# thar_board_general_mk1.net
KiCad netlist of a schematic drawn in EAGLE
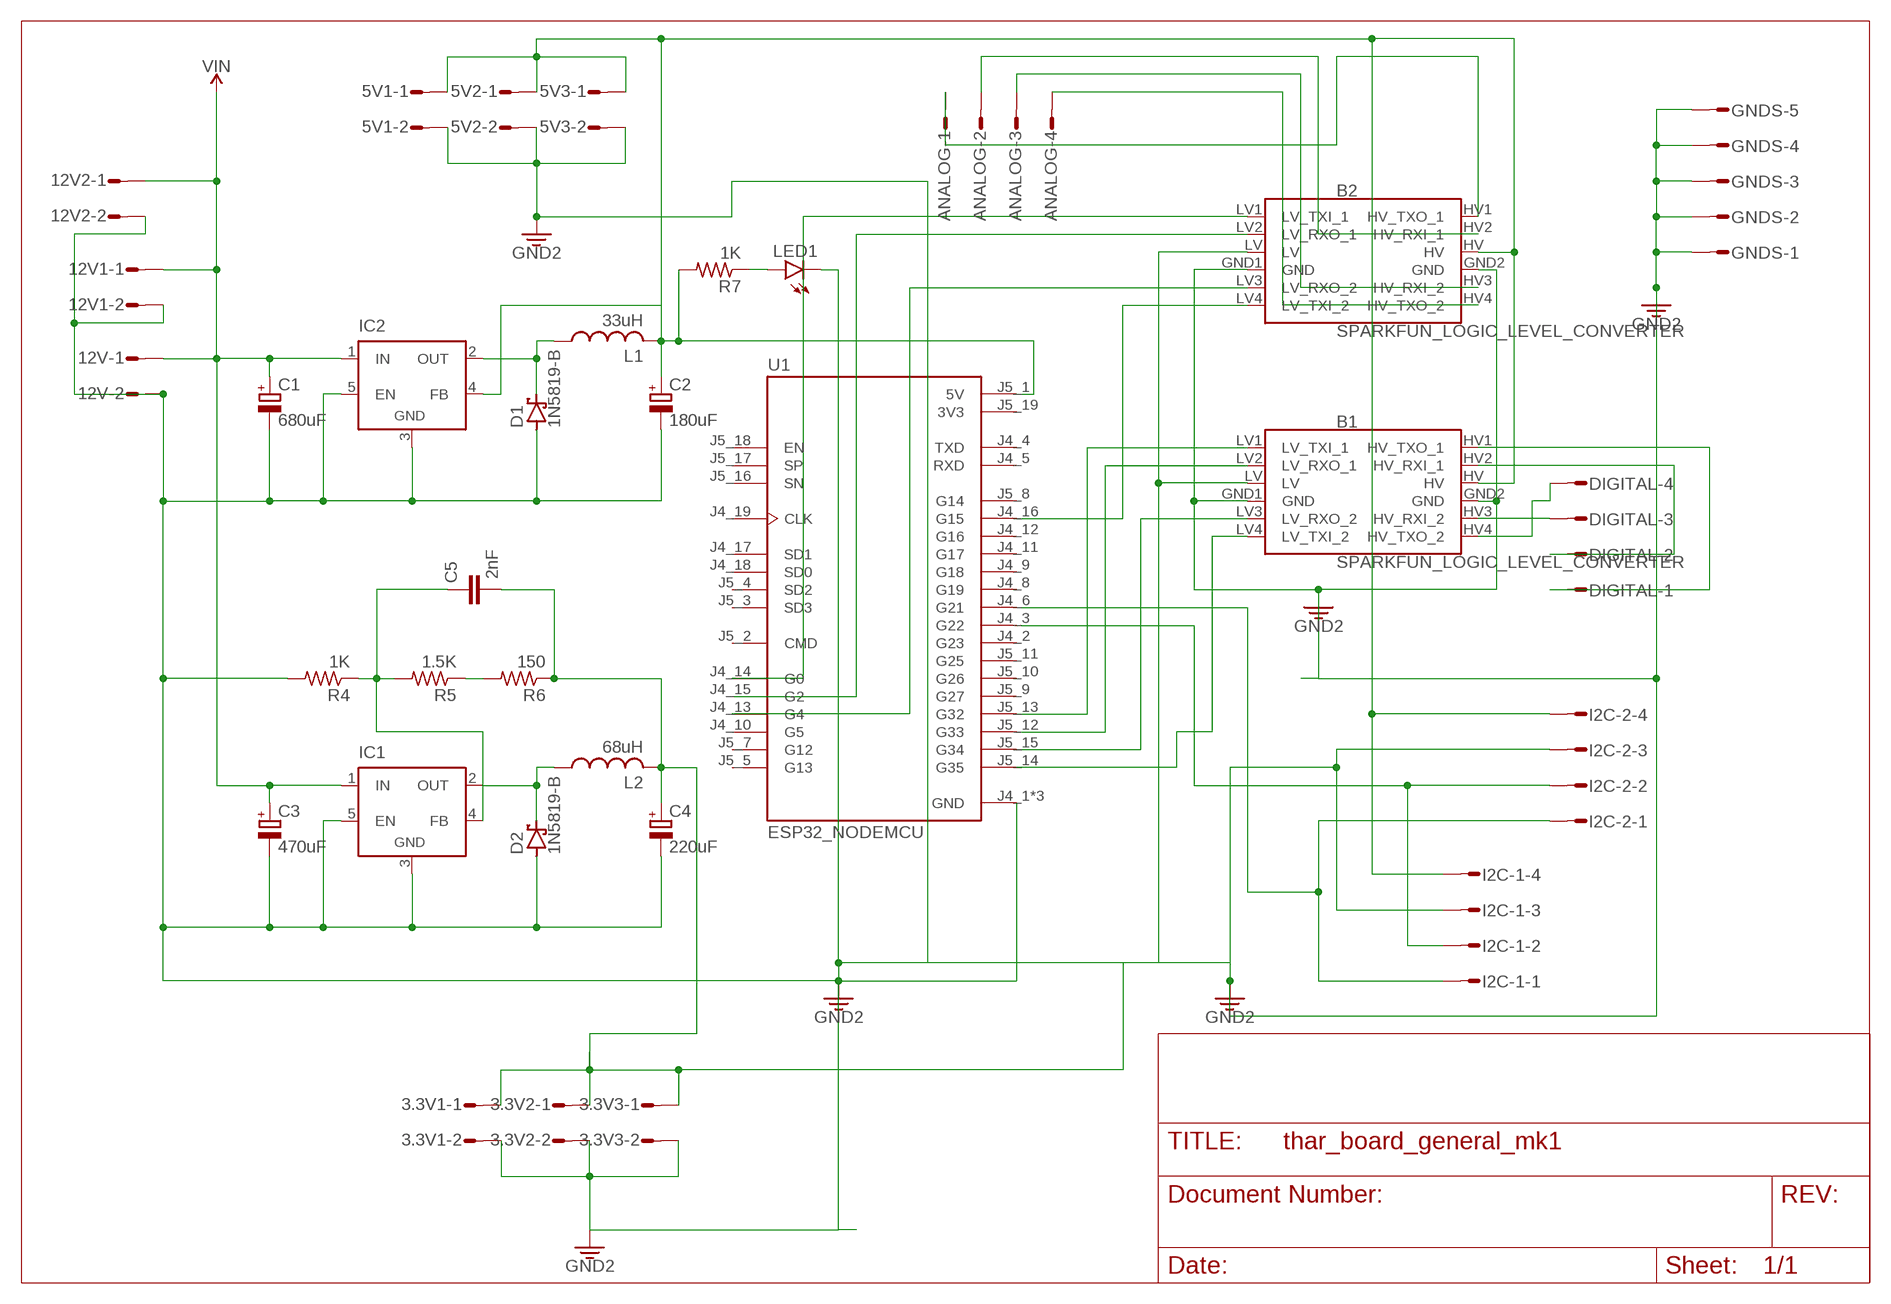
[diagram p0: schematic, sheet 1]

(export (version "E")
  (design (tool "Eeschema 10.0.6"))
  (components
    (comp (ref "3.3V1")
      (value "L02P")
      (footprint "eagle-import:L02P")
      (libsource (lib "eagle-import") (part "L02P"))
    )
    (comp (ref "3.3V2")
      (value "L02P")
      (footprint "eagle-import:L02P")
      (libsource (lib "eagle-import") (part "L02P"))
    )
    (comp (ref "3.3V3")
      (value "L02P")
      (footprint "eagle-import:L02P")
      (libsource (lib "eagle-import") (part "L02P"))
    )
    (comp (ref "5V1")
      (value "L02P")
      (footprint "eagle-import:L02P")
      (libsource (lib "eagle-import") (part "L02P"))
    )
    (comp (ref "5V2")
      (value "L02P")
      (footprint "eagle-import:L02P")
      (libsource (lib "eagle-import") (part "L02P"))
    )
    (comp (ref "5V3")
      (value "L02P")
      (footprint "eagle-import:L02P")
      (libsource (lib "eagle-import") (part "L02P"))
    )
    (comp (ref "12V")
      (value "L02P")
      (footprint "eagle-import:L02P")
      (libsource (lib "eagle-import") (part "L02P"))
    )
    (comp (ref "12V1")
      (value "L02P")
      (footprint "eagle-import:L02P")
      (libsource (lib "eagle-import") (part "L02P"))
    )
    (comp (ref "12V2")
      (value "L02P")
      (footprint "eagle-import:L02P")
      (libsource (lib "eagle-import") (part "L02P"))
    )
    (comp (ref "ANALOG")
      (value "L04P")
      (footprint "eagle-import:L04P")
      (libsource (lib "eagle-import") (part "L04P"))
    )
    (comp (ref "B1")
      (value "SPARKFUN_LOGIC_LEVEL_CONVERTER")
      (footprint "eagle-import:SPARKFUN_LOGIC_LEVEL_CONVERTER")
      (libsource (lib "eagle-import") (part "SPARKFUN_LOGIC_LEVEL_CONVERTER"))
    )
    (comp (ref "B2")
      (value "SPARKFUN_LOGIC_LEVEL_CONVERTER")
      (footprint "eagle-import:SPARKFUN_LOGIC_LEVEL_CONVERTER")
      (libsource (lib "eagle-import") (part "SPARKFUN_LOGIC_LEVEL_CONVERTER"))
    )
    (comp (ref "C1")
      (value "680uF")
      (footprint "eagle-import:E2,5-7")
      (libsource (lib "eagle-import") (part "CPOL-EUE2.5-7"))
    )
    (comp (ref "C2")
      (value "180uF")
      (footprint "eagle-import:E2,5-7")
      (libsource (lib "eagle-import") (part "CPOL-EUE2.5-7"))
    )
    (comp (ref "C3")
      (value "470uF")
      (footprint "eagle-import:E2,5-7")
      (libsource (lib "eagle-import") (part "CPOL-EUE2.5-7"))
    )
    (comp (ref "C4")
      (value "220uF")
      (footprint "eagle-import:E2,5-7")
      (libsource (lib "eagle-import") (part "CPOL-EUE2.5-7"))
    )
    (comp (ref "C5")
      (value "2nF")
      (footprint "eagle-import:C025-025X050")
      (libsource (lib "eagle-import") (part "C-EU025-025X050"))
    )
    (comp (ref "D1")
      (value "1N5819-B")
      (footprint "eagle-import:DO41-7.6")
      (libsource (lib "eagle-import") (part "1N5819-B"))
    )
    (comp (ref "D2")
      (value "1N5819-B")
      (footprint "eagle-import:DO41-7.6")
      (libsource (lib "eagle-import") (part "1N5819-B"))
    )
    (comp (ref "DIGITAL")
      (value "L04P")
      (footprint "eagle-import:L04P")
      (libsource (lib "eagle-import") (part "L04P"))
    )
    (comp (ref "GNDS")
      (value "L05P")
      (footprint "eagle-import:L05P")
      (libsource (lib "eagle-import") (part "L05P"))
    )
    (comp (ref "I2C-1")
      (value "L04P")
      (footprint "eagle-import:L04P")
      (libsource (lib "eagle-import") (part "L04P"))
    )
    (comp (ref "I2C-2")
      (value "L04P")
      (footprint "eagle-import:L04P")
      (libsource (lib "eagle-import") (part "L04P"))
    )
    (comp (ref "IC1")
      (value "LM2596TH")
      (footprint "eagle-import:TO220-52")
      (libsource (lib "eagle-import") (part "LM2596TH"))
    )
    (comp (ref "IC2")
      (value "LM2596TH")
      (footprint "eagle-import:TO220-52")
      (libsource (lib "eagle-import") (part "LM2596TH"))
    )
    (comp (ref "L1")
      (value "33uH")
      (footprint "eagle-import:TFI0410")
      (libsource (lib "eagle-import") (part "L-USTFI0410"))
    )
    (comp (ref "L2")
      (value "68uH")
      (footprint "eagle-import:TFI0410")
      (libsource (lib "eagle-import") (part "L-USTFI0410"))
    )
    (comp (ref "LED1")
      (value "LED3MM")
      (footprint "eagle-import:LED3MM")
      (libsource (lib "eagle-import") (part "LED3MM"))
    )
    (comp (ref "R4")
      (value "1K")
      (footprint "eagle-import:0207_10")
      (libsource (lib "eagle-import") (part "R-US_0207/10"))
    )
    (comp (ref "R5")
      (value "1.5K")
      (footprint "eagle-import:0207_10")
      (libsource (lib "eagle-import") (part "R-US_0207/10"))
    )
    (comp (ref "R6")
      (value "150")
      (footprint "eagle-import:0207_10")
      (libsource (lib "eagle-import") (part "R-US_0207/10"))
    )
    (comp (ref "R7")
      (value "1K")
      (footprint "eagle-import:0207_10")
      (libsource (lib "eagle-import") (part "R-US_0207/10"))
    )
    (comp (ref "U1")
      (value "ESP32_NODEMCU")
      (footprint "eagle-import:MODULE_ESP32_NODEMCU")
      (fields (field (name "MF") "Espressif Systems") (field (name "MP") "ESP32 NodeMCU"))
      (libsource (lib "eagle-import") (part "ESP32_NODEMCU"))
    )
  )
  (nets
    (net (code "1") (name "/3V3") (class "Default")
      (node (ref "U1") (pin "J5_19") (pinfunction "3V3_J5_19") (pintype "power_in"))
    )
    (net (code "2") (name "GND2") (class "Default")
      (node (ref "12V") (pin "2") (pinfunction "S_2") (pintype "passive"))
      (node (ref "12V1") (pin "2") (pinfunction "S_2") (pintype "passive"))
      (node (ref "12V2") (pin "2") (pinfunction "S_2") (pintype "passive"))
      (node (ref "3.3V1") (pin "2") (pinfunction "S_2") (pintype "passive"))
      (node (ref "3.3V2") (pin "2") (pinfunction "S_2") (pintype "passive"))
      (node (ref "3.3V3") (pin "2") (pinfunction "S_2") (pintype "passive"))
      (node (ref "5V1") (pin "2") (pinfunction "S_2") (pintype "passive"))
      (node (ref "5V2") (pin "2") (pinfunction "S_2") (pintype "passive"))
      (node (ref "5V3") (pin "2") (pinfunction "S_2") (pintype "passive"))
      (node (ref "B1") (pin "GND1") (pinfunction "GND_GND1") (pintype "power_in"))
      (node (ref "B1") (pin "GND2") (pinfunction "GND_GND2") (pintype "power_in"))
      (node (ref "B2") (pin "GND1") (pinfunction "GND_GND1") (pintype "power_in"))
      (node (ref "B2") (pin "GND2") (pinfunction "GND_GND2") (pintype "power_in"))
      (node (ref "C1") (pin "-") (pinfunction "-_-") (pintype "passive"))
      (node (ref "C2") (pin "-") (pinfunction "-_-") (pintype "passive"))
      (node (ref "C3") (pin "-") (pinfunction "-_-") (pintype "passive"))
      (node (ref "C4") (pin "-") (pinfunction "-_-") (pintype "passive"))
      (node (ref "D1") (pin "A") (pinfunction "A_A") (pintype "passive"))
      (node (ref "D2") (pin "A") (pinfunction "A_A") (pintype "passive"))
      (node (ref "GNDS") (pin "1") (pinfunction "S_1") (pintype "passive"))
      (node (ref "GNDS") (pin "2") (pinfunction "S_2") (pintype "passive"))
      (node (ref "GNDS") (pin "3") (pinfunction "S_3") (pintype "passive"))
      (node (ref "GNDS") (pin "4") (pinfunction "S_4") (pintype "passive"))
      (node (ref "GNDS") (pin "5") (pinfunction "S_5") (pintype "passive"))
      (node (ref "I2C-1") (pin "3") (pinfunction "S_3") (pintype "passive"))
      (node (ref "I2C-2") (pin "3") (pinfunction "S_3") (pintype "passive"))
      (node (ref "IC1") (pin "3") (pinfunction "GND_3") (pintype "power_in"))
      (node (ref "IC1") (pin "5") (pinfunction "EN_5") (pintype "input"))
      (node (ref "IC2") (pin "3") (pinfunction "GND_3") (pintype "power_in"))
      (node (ref "IC2") (pin "5") (pinfunction "EN_5") (pintype "input"))
      (node (ref "LED1") (pin "K") (pinfunction "C_K") (pintype "passive"))
      (node (ref "R4") (pin "2") (pinfunction "2_2") (pintype "passive"))
      (node (ref "U1") (pin "J4_1") (pinfunction "GND_J4_1") (pintype "power_in"))
      (node (ref "U1") (pin "J4_7") (pinfunction "GND_J4_7") (pintype "power_in"))
      (node (ref "U1") (pin "J5_6") (pinfunction "GND_J5_6") (pintype "power_in"))
    )
    (net (code "3") (name "Net-(3.3V1A-S)") (class "Default")
      (node (ref "3.3V1") (pin "1") (pinfunction "S_1") (pintype "passive"))
      (node (ref "3.3V2") (pin "1") (pinfunction "S_1") (pintype "passive"))
      (node (ref "3.3V3") (pin "1") (pinfunction "S_1") (pintype "passive"))
      (node (ref "B1") (pin "LV") (pinfunction "LV_LV") (pintype "power_in"))
      (node (ref "B2") (pin "LV") (pinfunction "LV_LV") (pintype "power_in"))
      (node (ref "C4") (pin "+") (pinfunction "+_+") (pintype "passive"))
      (node (ref "C5") (pin "2") (pinfunction "2_2") (pintype "passive"))
      (node (ref "L2") (pin "2") (pinfunction "2_2") (pintype "passive"))
      (node (ref "R6") (pin "1") (pinfunction "1_1") (pintype "passive"))
    )
    (net (code "4") (name "Net-(5V1A-S)") (class "Default")
      (node (ref "5V1") (pin "1") (pinfunction "S_1") (pintype "passive"))
      (node (ref "5V2") (pin "1") (pinfunction "S_1") (pintype "passive"))
      (node (ref "5V3") (pin "1") (pinfunction "S_1") (pintype "passive"))
      (node (ref "B1") (pin "HV") (pinfunction "HV_HV") (pintype "power_in"))
      (node (ref "B2") (pin "HV") (pinfunction "HV_HV") (pintype "power_in"))
      (node (ref "C2") (pin "+") (pinfunction "+_+") (pintype "passive"))
      (node (ref "I2C-1") (pin "4") (pinfunction "S_4") (pintype "passive"))
      (node (ref "I2C-2") (pin "4") (pinfunction "S_4") (pintype "passive"))
      (node (ref "IC2") (pin "4") (pinfunction "FB_4") (pintype "input"))
      (node (ref "L1") (pin "2") (pinfunction "2_2") (pintype "passive"))
      (node (ref "R7") (pin "2") (pinfunction "2_2") (pintype "passive"))
      (node (ref "U1") (pin "J5_1") (pinfunction "5V_J5_1") (pintype "power_in"))
    )
    (net (code "5") (name "Net-(ANALOGA-S)") (class "Default")
      (node (ref "ANALOG") (pin "1") (pinfunction "S_1") (pintype "passive"))
      (node (ref "B2") (pin "HV1") (pinfunction "HV_TXO_1_HV1") (pintype "bidirectional"))
    )
    (net (code "6") (name "Net-(ANALOGB-S)") (class "Default")
      (node (ref "ANALOG") (pin "2") (pinfunction "S_2") (pintype "passive"))
      (node (ref "B2") (pin "HV2") (pinfunction "HV_RXI_1_HV2") (pintype "bidirectional"))
    )
    (net (code "7") (name "Net-(ANALOGC-S)") (class "Default")
      (node (ref "ANALOG") (pin "3") (pinfunction "S_3") (pintype "passive"))
      (node (ref "B2") (pin "HV3") (pinfunction "HV_RXI_2_HV3") (pintype "bidirectional"))
    )
    (net (code "8") (name "Net-(ANALOGD-S)") (class "Default")
      (node (ref "ANALOG") (pin "4") (pinfunction "S_4") (pintype "passive"))
      (node (ref "B2") (pin "HV4") (pinfunction "HV_TXO_2_HV4") (pintype "bidirectional"))
    )
    (net (code "9") (name "Net-(B1-HV_RXI_1)") (class "Default")
      (node (ref "B1") (pin "HV2") (pinfunction "HV_RXI_1_HV2") (pintype "bidirectional"))
      (node (ref "DIGITAL") (pin "2") (pinfunction "S_2") (pintype "passive"))
    )
    (net (code "10") (name "Net-(B1-HV_RXI_2)") (class "Default")
      (node (ref "B1") (pin "HV3") (pinfunction "HV_RXI_2_HV3") (pintype "bidirectional"))
      (node (ref "DIGITAL") (pin "3") (pinfunction "S_3") (pintype "passive"))
    )
    (net (code "11") (name "Net-(B1-HV_TXO_1)") (class "Default")
      (node (ref "B1") (pin "HV1") (pinfunction "HV_TXO_1_HV1") (pintype "bidirectional"))
      (node (ref "DIGITAL") (pin "1") (pinfunction "S_1") (pintype "passive"))
    )
    (net (code "12") (name "Net-(B1-HV_TXO_2)") (class "Default")
      (node (ref "B1") (pin "HV4") (pinfunction "HV_TXO_2_HV4") (pintype "bidirectional"))
      (node (ref "DIGITAL") (pin "4") (pinfunction "S_4") (pintype "passive"))
    )
    (net (code "13") (name "Net-(B1-LV_RXO_1)") (class "Default")
      (node (ref "B1") (pin "LV2") (pinfunction "LV_RXO_1_LV2") (pintype "bidirectional"))
      (node (ref "U1") (pin "J5_12") (pinfunction "G33_J5_12") (pintype "bidirectional"))
    )
    (net (code "14") (name "Net-(B1-LV_RXO_2)") (class "Default")
      (node (ref "B1") (pin "LV3") (pinfunction "LV_RXO_2_LV3") (pintype "bidirectional"))
      (node (ref "U1") (pin "J5_15") (pinfunction "G34_J5_15") (pintype "bidirectional"))
    )
    (net (code "15") (name "Net-(B1-LV_TXI_1)") (class "Default")
      (node (ref "B1") (pin "LV1") (pinfunction "LV_TXI_1_LV1") (pintype "bidirectional"))
      (node (ref "U1") (pin "J5_13") (pinfunction "G32_J5_13") (pintype "bidirectional"))
    )
    (net (code "16") (name "Net-(B1-LV_TXI_2)") (class "Default")
      (node (ref "B1") (pin "LV4") (pinfunction "LV_TXI_2_LV4") (pintype "bidirectional"))
      (node (ref "U1") (pin "J5_14") (pinfunction "G35_J5_14") (pintype "bidirectional"))
    )
    (net (code "17") (name "Net-(B2-LV_RXO_1)") (class "Default")
      (node (ref "B2") (pin "LV2") (pinfunction "LV_RXO_1_LV2") (pintype "bidirectional"))
      (node (ref "U1") (pin "J4_15") (pinfunction "G2_J4_15") (pintype "bidirectional"))
    )
    (net (code "18") (name "Net-(B2-LV_RXO_2)") (class "Default")
      (node (ref "B2") (pin "LV3") (pinfunction "LV_RXO_2_LV3") (pintype "bidirectional"))
      (node (ref "U1") (pin "J4_13") (pinfunction "G4_J4_13") (pintype "bidirectional"))
    )
    (net (code "19") (name "Net-(B2-LV_TXI_1)") (class "Default")
      (node (ref "B2") (pin "LV1") (pinfunction "LV_TXI_1_LV1") (pintype "bidirectional"))
      (node (ref "U1") (pin "J4_14") (pinfunction "G0_J4_14") (pintype "bidirectional"))
    )
    (net (code "20") (name "Net-(B2-LV_TXI_2)") (class "Default")
      (node (ref "B2") (pin "LV4") (pinfunction "LV_TXI_2_LV4") (pintype "bidirectional"))
      (node (ref "U1") (pin "J4_16") (pinfunction "G15_J4_16") (pintype "bidirectional"))
    )
    (net (code "21") (name "Net-(I2C-1A-S)") (class "Default")
      (node (ref "I2C-1") (pin "1") (pinfunction "S_1") (pintype "passive"))
      (node (ref "I2C-2") (pin "1") (pinfunction "S_1") (pintype "passive"))
      (node (ref "U1") (pin "J4_6") (pinfunction "G21_J4_6") (pintype "bidirectional"))
    )
    (net (code "22") (name "Net-(I2C-1B-S)") (class "Default")
      (node (ref "I2C-1") (pin "2") (pinfunction "S_2") (pintype "passive"))
      (node (ref "I2C-2") (pin "2") (pinfunction "S_2") (pintype "passive"))
      (node (ref "U1") (pin "J4_3") (pinfunction "G22_J4_3") (pintype "bidirectional"))
    )
    (net (code "23") (name "Net-(IC1-FB)") (class "Default")
      (node (ref "C5") (pin "1") (pinfunction "1_1") (pintype "passive"))
      (node (ref "IC1") (pin "4") (pinfunction "FB_4") (pintype "input"))
      (node (ref "R4") (pin "1") (pinfunction "1_1") (pintype "passive"))
      (node (ref "R5") (pin "2") (pinfunction "2_2") (pintype "passive"))
    )
    (net (code "24") (name "Net-(IC1-OUT)") (class "Default")
      (node (ref "D2") (pin "C") (pinfunction "C_C") (pintype "passive"))
      (node (ref "IC1") (pin "2") (pinfunction "OUT_2") (pintype "output"))
      (node (ref "L2") (pin "1") (pinfunction "1_1") (pintype "passive"))
    )
    (net (code "25") (name "Net-(IC2-OUT)") (class "Default")
      (node (ref "D1") (pin "C") (pinfunction "C_C") (pintype "passive"))
      (node (ref "IC2") (pin "2") (pinfunction "OUT_2") (pintype "output"))
      (node (ref "L1") (pin "1") (pinfunction "1_1") (pintype "passive"))
    )
    (net (code "26") (name "Net-(LED1-PadA)") (class "Default")
      (node (ref "LED1") (pin "A") (pinfunction "A_A") (pintype "passive"))
      (node (ref "R7") (pin "1") (pinfunction "1_1") (pintype "passive"))
    )
    (net (code "27") (name "Net-(R5-Pad1)") (class "Default")
      (node (ref "R5") (pin "1") (pinfunction "1_1") (pintype "passive"))
      (node (ref "R6") (pin "2") (pinfunction "2_2") (pintype "passive"))
    )
    (net (code "28") (name "VIN") (class "Default")
      (node (ref "12V") (pin "1") (pinfunction "S_1") (pintype "passive"))
      (node (ref "12V1") (pin "1") (pinfunction "S_1") (pintype "passive"))
      (node (ref "12V2") (pin "1") (pinfunction "S_1") (pintype "passive"))
      (node (ref "C1") (pin "+") (pinfunction "+_+") (pintype "passive"))
      (node (ref "C3") (pin "+") (pinfunction "+_+") (pintype "passive"))
      (node (ref "IC1") (pin "1") (pinfunction "IN_1") (pintype "input"))
      (node (ref "IC2") (pin "1") (pinfunction "IN_1") (pintype "input"))
    )
    (net (code "29") (name "unconnected-(U1-CLK-PadJ4_19)") (class "Default")
      (node (ref "U1") (pin "J4_19") (pinfunction "CLK_J4_19") (pintype "input"))
    )
    (net (code "30") (name "unconnected-(U1-CMD-PadJ5_2)") (class "Default")
      (node (ref "U1") (pin "J5_2") (pinfunction "CMD_J5_2") (pintype "bidirectional"))
    )
    (net (code "31") (name "unconnected-(U1-EN-PadJ5_18)") (class "Default")
      (node (ref "U1") (pin "J5_18") (pinfunction "EN_J5_18") (pintype "input"))
    )
    (net (code "32") (name "unconnected-(U1-G5-PadJ4_10)") (class "Default")
      (node (ref "U1") (pin "J4_10") (pinfunction "G5_J4_10") (pintype "bidirectional"))
    )
    (net (code "33") (name "unconnected-(U1-G12-PadJ5_7)") (class "Default")
      (node (ref "U1") (pin "J5_7") (pinfunction "G12_J5_7") (pintype "bidirectional"))
    )
    (net (code "34") (name "unconnected-(U1-G13-PadJ5_5)") (class "Default")
      (node (ref "U1") (pin "J5_5") (pinfunction "G13_J5_5") (pintype "bidirectional"))
    )
    (net (code "35") (name "unconnected-(U1-G14-PadJ5_8)") (class "Default")
      (node (ref "U1") (pin "J5_8") (pinfunction "G14_J5_8") (pintype "bidirectional"))
    )
    (net (code "36") (name "unconnected-(U1-G16-PadJ4_12)") (class "Default")
      (node (ref "U1") (pin "J4_12") (pinfunction "G16_J4_12") (pintype "bidirectional"))
    )
    (net (code "37") (name "unconnected-(U1-G17-PadJ4_11)") (class "Default")
      (node (ref "U1") (pin "J4_11") (pinfunction "G17_J4_11") (pintype "bidirectional"))
    )
    (net (code "38") (name "unconnected-(U1-G18-PadJ4_9)") (class "Default")
      (node (ref "U1") (pin "J4_9") (pinfunction "G18_J4_9") (pintype "bidirectional"))
    )
    (net (code "39") (name "unconnected-(U1-G19-PadJ4_8)") (class "Default")
      (node (ref "U1") (pin "J4_8") (pinfunction "G19_J4_8") (pintype "bidirectional"))
    )
    (net (code "40") (name "unconnected-(U1-G23-PadJ4_2)") (class "Default")
      (node (ref "U1") (pin "J4_2") (pinfunction "G23_J4_2") (pintype "bidirectional"))
    )
    (net (code "41") (name "unconnected-(U1-G25-PadJ5_11)") (class "Default")
      (node (ref "U1") (pin "J5_11") (pinfunction "G25_J5_11") (pintype "bidirectional"))
    )
    (net (code "42") (name "unconnected-(U1-G26-PadJ5_10)") (class "Default")
      (node (ref "U1") (pin "J5_10") (pinfunction "G26_J5_10") (pintype "bidirectional"))
    )
    (net (code "43") (name "unconnected-(U1-G27-PadJ5_9)") (class "Default")
      (node (ref "U1") (pin "J5_9") (pinfunction "G27_J5_9") (pintype "bidirectional"))
    )
    (net (code "44") (name "unconnected-(U1-RXD-PadJ4_5)") (class "Default")
      (node (ref "U1") (pin "J4_5") (pinfunction "RXD_J4_5") (pintype "input"))
    )
    (net (code "45") (name "unconnected-(U1-SD0-PadJ4_18)") (class "Default")
      (node (ref "U1") (pin "J4_18") (pinfunction "SD0_J4_18") (pintype "bidirectional"))
    )
    (net (code "46") (name "unconnected-(U1-SD1-PadJ4_17)") (class "Default")
      (node (ref "U1") (pin "J4_17") (pinfunction "SD1_J4_17") (pintype "bidirectional"))
    )
    (net (code "47") (name "unconnected-(U1-SD2-PadJ5_4)") (class "Default")
      (node (ref "U1") (pin "J5_4") (pinfunction "SD2_J5_4") (pintype "bidirectional"))
    )
    (net (code "48") (name "unconnected-(U1-SD3-PadJ5_3)") (class "Default")
      (node (ref "U1") (pin "J5_3") (pinfunction "SD3_J5_3") (pintype "bidirectional"))
    )
    (net (code "49") (name "unconnected-(U1-SN-PadJ5_16)") (class "Default")
      (node (ref "U1") (pin "J5_16") (pinfunction "SN_J5_16") (pintype "input"))
    )
    (net (code "50") (name "unconnected-(U1-SP-PadJ5_17)") (class "Default")
      (node (ref "U1") (pin "J5_17") (pinfunction "SP_J5_17") (pintype "input"))
    )
    (net (code "51") (name "unconnected-(U1-TXD-PadJ4_4)") (class "Default")
      (node (ref "U1") (pin "J4_4") (pinfunction "TXD_J4_4") (pintype "output"))
    )
  )
)
